# CP_schem.net
KiCad netlist of a schematic drawn in Altium Designer
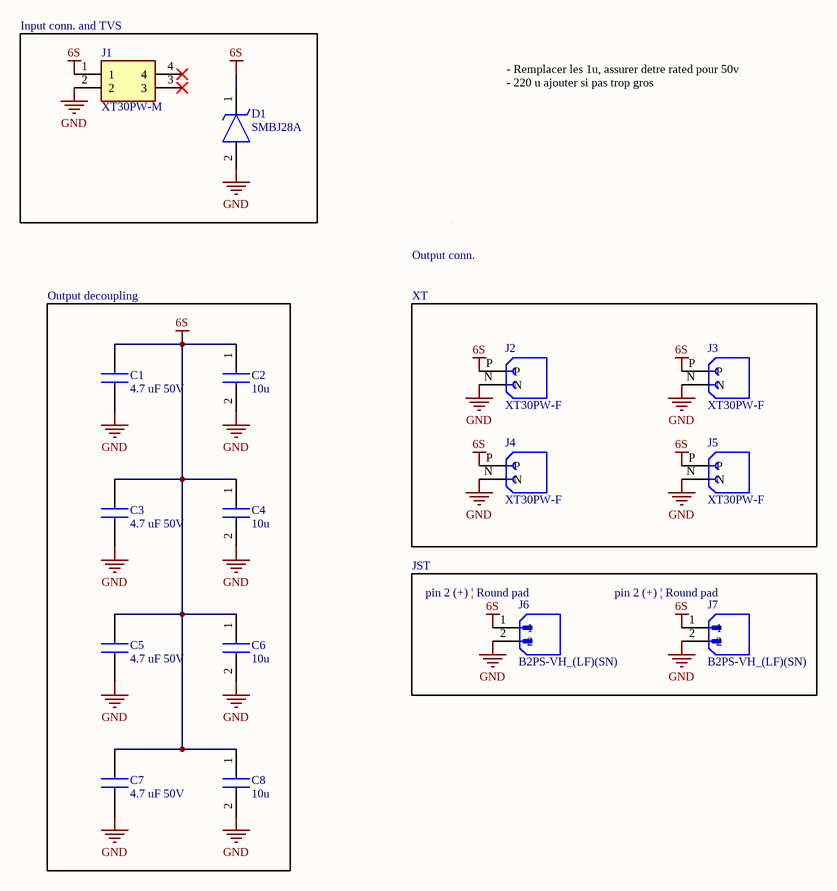
[diagram p0: CP_schem.SchDoc]

(export (version "E")
  (design (tool "Eeschema 10.0.6"))
  (components
    (comp (ref "C1")
      (value "4.7 uF 50V")
      (footprint "CAPC2012X145N")
      (description "Capacitor")
      (fields
        (field (name "MANUFACTURER_PART_NUMBER") "GRM21BR61H475KE51L")
        (field (name "MOUSER PART NUMBER") "81-GRM21BR61H475KE1L")
      )
      (libsource (lib "Symbol_library") (part "GRM21BR61H475KE51L"))
    )
    (comp (ref "C2")
      (value "10u")
      (footprint "SamacSys:GRM32x")
      (description "Capacitor")
      (fields
        (field (name "MANUFACTURER_PART_NUMBER") "GRM32EC72A106ME05L")
        (field (name "MOUSER PART NUMBER") "81-GRM32EC72A106ME5L")
      )
      (libsource (lib "*") (part "GRM32EC72A106ME05L"))
    )
    (comp (ref "C3")
      (value "4.7 uF 50V")
      (footprint "CAPC2012X145N")
      (description "Capacitor")
      (fields
        (field (name "MANUFACTURER_PART_NUMBER") "GRM21BR61H475KE51L")
        (field (name "MOUSER PART NUMBER") "81-GRM21BR61H475KE1L")
      )
      (libsource (lib "Symbol_library") (part "GRM21BR61H475KE51L"))
    )
    (comp (ref "C4")
      (value "10u")
      (footprint "SamacSys:GRM32x")
      (description "Capacitor")
      (fields
        (field (name "MANUFACTURER_PART_NUMBER") "GRM32EC72A106ME05L")
        (field (name "MOUSER PART NUMBER") "81-GRM32EC72A106ME5L")
      )
      (libsource (lib "*") (part "GRM32EC72A106ME05L"))
    )
    (comp (ref "C5")
      (value "4.7 uF 50V")
      (footprint "CAPC2012X145N")
      (description "Capacitor")
      (fields
        (field (name "MANUFACTURER_PART_NUMBER") "GRM21BR61H475KE51L")
        (field (name "MOUSER PART NUMBER") "81-GRM21BR61H475KE1L")
      )
      (libsource (lib "Symbol_library") (part "GRM21BR61H475KE51L"))
    )
    (comp (ref "C6")
      (value "10u")
      (footprint "SamacSys:GRM32x")
      (description "Capacitor")
      (fields
        (field (name "MANUFACTURER_PART_NUMBER") "GRM32EC72A106ME05L")
        (field (name "MOUSER PART NUMBER") "81-GRM32EC72A106ME5L")
      )
      (libsource (lib "*") (part "GRM32EC72A106ME05L"))
    )
    (comp (ref "C7")
      (value "4.7 uF 50V")
      (footprint "CAPC2012X145N")
      (description "Capacitor")
      (fields
        (field (name "MANUFACTURER_PART_NUMBER") "GRM21BR61H475KE51L")
        (field (name "MOUSER PART NUMBER") "81-GRM21BR61H475KE1L")
      )
      (libsource (lib "Symbol_library") (part "GRM21BR61H475KE51L"))
    )
    (comp (ref "C8")
      (value "10u")
      (footprint "SamacSys:GRM32x")
      (description "Capacitor")
      (fields
        (field (name "MANUFACTURER_PART_NUMBER") "GRM32EC72A106ME05L")
        (field (name "MOUSER PART NUMBER") "81-GRM32EC72A106ME5L")
      )
      (libsource (lib "*") (part "GRM32EC72A106ME05L"))
    )
    (comp (ref "D1")
      (value "SMBJ28A")
      (footprint "SamacSys:SMBJ12A")
      (description "TVS Diode (Uni-directional)")
      (libsource (lib "*") (part "SMBJ28A"))
    )
    (comp (ref "J1")
      (value "XT30PW-M")
      (footprint "SamacSys:XT30PWM")
      (description "Connector")
      (libsource (lib "*") (part "XT30PW-M"))
    )
    (comp (ref "J2")
      (value "XT30PW-F")
      (footprint "AMASS_XT30PW-F")
      (description "Socket; DC supply; XT30; female; PIN: 2; on PCBs; THT; yellow; 15A")
      (fields (field (name "MF") "amass"))
      (libsource (lib "Symbol_library") (part "XT30PW-F"))
    )
    (comp (ref "J3")
      (value "XT30PW-F")
      (footprint "AMASS_XT30PW-F")
      (description "Socket; DC supply; XT30; female; PIN: 2; on PCBs; THT; yellow; 15A")
      (fields (field (name "MF") "amass"))
      (libsource (lib "Symbol_library") (part "XT30PW-F"))
    )
    (comp (ref "J4")
      (value "XT30PW-F")
      (footprint "AMASS_XT30PW-F")
      (description "Socket; DC supply; XT30; female; PIN: 2; on PCBs; THT; yellow; 15A")
      (fields (field (name "MF") "amass"))
      (libsource (lib "Symbol_library") (part "XT30PW-F"))
    )
    (comp (ref "J5")
      (value "XT30PW-F")
      (footprint "AMASS_XT30PW-F")
      (description "Socket; DC supply; XT30; female; PIN: 2; on PCBs; THT; yellow; 15A")
      (fields (field (name "MF") "amass"))
      (libsource (lib "Symbol_library") (part "XT30PW-F"))
    )
    (comp (ref "J6")
      (value "B2PS-VH_(LF)(SN)")
      (footprint "JST_B2PS-VH_(LF)(SN)")
      (description "Connector Header Through Hole, Right Angle 2 position 0.156 (3.96mm)")
      (fields (field (name "MF") "JST") (field (name "MP") "B2PS-VH (LF)(SN)"))
      (libsource (lib "Symbol_library") (part "B2PS-VH_(LF)(SN)"))
    )
    (comp (ref "J7")
      (value "B2PS-VH_(LF)(SN)")
      (footprint "JST_B2PS-VH_(LF)(SN)")
      (description "Connector Header Through Hole, Right Angle 2 position 0.156 (3.96mm)")
      (fields (field (name "MF") "JST") (field (name "MP") "B2PS-VH (LF)(SN)"))
      (libsource (lib "Symbol_library") (part "B2PS-VH_(LF)(SN)"))
    )
  )
  (nets
    (net (code "1") (name "6S") (class "Default")
      (node (ref "C1") (pin "1") (pinfunction "1_1") (pintype "passive"))
      (node (ref "C2") (pin "1") (pinfunction "1_1") (pintype "passive"))
      (node (ref "C3") (pin "1") (pinfunction "1_1") (pintype "passive"))
      (node (ref "C4") (pin "1") (pinfunction "1_1") (pintype "passive"))
      (node (ref "C5") (pin "1") (pinfunction "1_1") (pintype "passive"))
      (node (ref "C6") (pin "1") (pinfunction "1_1") (pintype "passive"))
      (node (ref "C7") (pin "1") (pinfunction "1_1") (pintype "passive"))
      (node (ref "C8") (pin "1") (pinfunction "1_1") (pintype "passive"))
      (node (ref "D1") (pin "1") (pinfunction "K_1") (pintype "passive"))
      (node (ref "J1") (pin "1") (pinfunction "1_1") (pintype "passive"))
      (node (ref "J2") (pin "P") (pinfunction "P_P") (pintype "power_in"))
      (node (ref "J3") (pin "P") (pinfunction "P_P") (pintype "power_in"))
      (node (ref "J4") (pin "P") (pinfunction "P_P") (pintype "power_in"))
      (node (ref "J5") (pin "P") (pinfunction "P_P") (pintype "power_in"))
      (node (ref "J6") (pin "1") (pinfunction "1_1") (pintype "passive"))
      (node (ref "J7") (pin "1") (pinfunction "1_1") (pintype "passive"))
    )
    (net (code "2") (name "GND") (class "Default")
      (node (ref "C1") (pin "2") (pinfunction "2_2") (pintype "passive"))
      (node (ref "C2") (pin "2") (pinfunction "2_2") (pintype "passive"))
      (node (ref "C3") (pin "2") (pinfunction "2_2") (pintype "passive"))
      (node (ref "C4") (pin "2") (pinfunction "2_2") (pintype "passive"))
      (node (ref "C5") (pin "2") (pinfunction "2_2") (pintype "passive"))
      (node (ref "C6") (pin "2") (pinfunction "2_2") (pintype "passive"))
      (node (ref "C7") (pin "2") (pinfunction "2_2") (pintype "passive"))
      (node (ref "C8") (pin "2") (pinfunction "2_2") (pintype "passive"))
      (node (ref "D1") (pin "2") (pinfunction "A_2") (pintype "passive"))
      (node (ref "J1") (pin "2") (pinfunction "2_2") (pintype "passive"))
      (node (ref "J2") (pin "N") (pinfunction "N_N") (pintype "power_in"))
      (node (ref "J3") (pin "N") (pinfunction "N_N") (pintype "power_in"))
      (node (ref "J4") (pin "N") (pinfunction "N_N") (pintype "power_in"))
      (node (ref "J5") (pin "N") (pinfunction "N_N") (pintype "power_in"))
      (node (ref "J6") (pin "2") (pinfunction "2_2") (pintype "passive"))
      (node (ref "J7") (pin "2") (pinfunction "2_2") (pintype "passive"))
    )
    (net (code "3") (name "unconnected-(J1-Pad3)") (class "Default")
      (node (ref "J1") (pin "3") (pinfunction "3_3") (pintype "passive+no_connect"))
    )
    (net (code "4") (name "unconnected-(J1-Pad4)") (class "Default")
      (node (ref "J1") (pin "4") (pinfunction "4_4") (pintype "passive+no_connect"))
    )
  )
)
